# STM_Basic_Extender.net
KiCad netlist of a schematic drawn in EasyEDA Pro
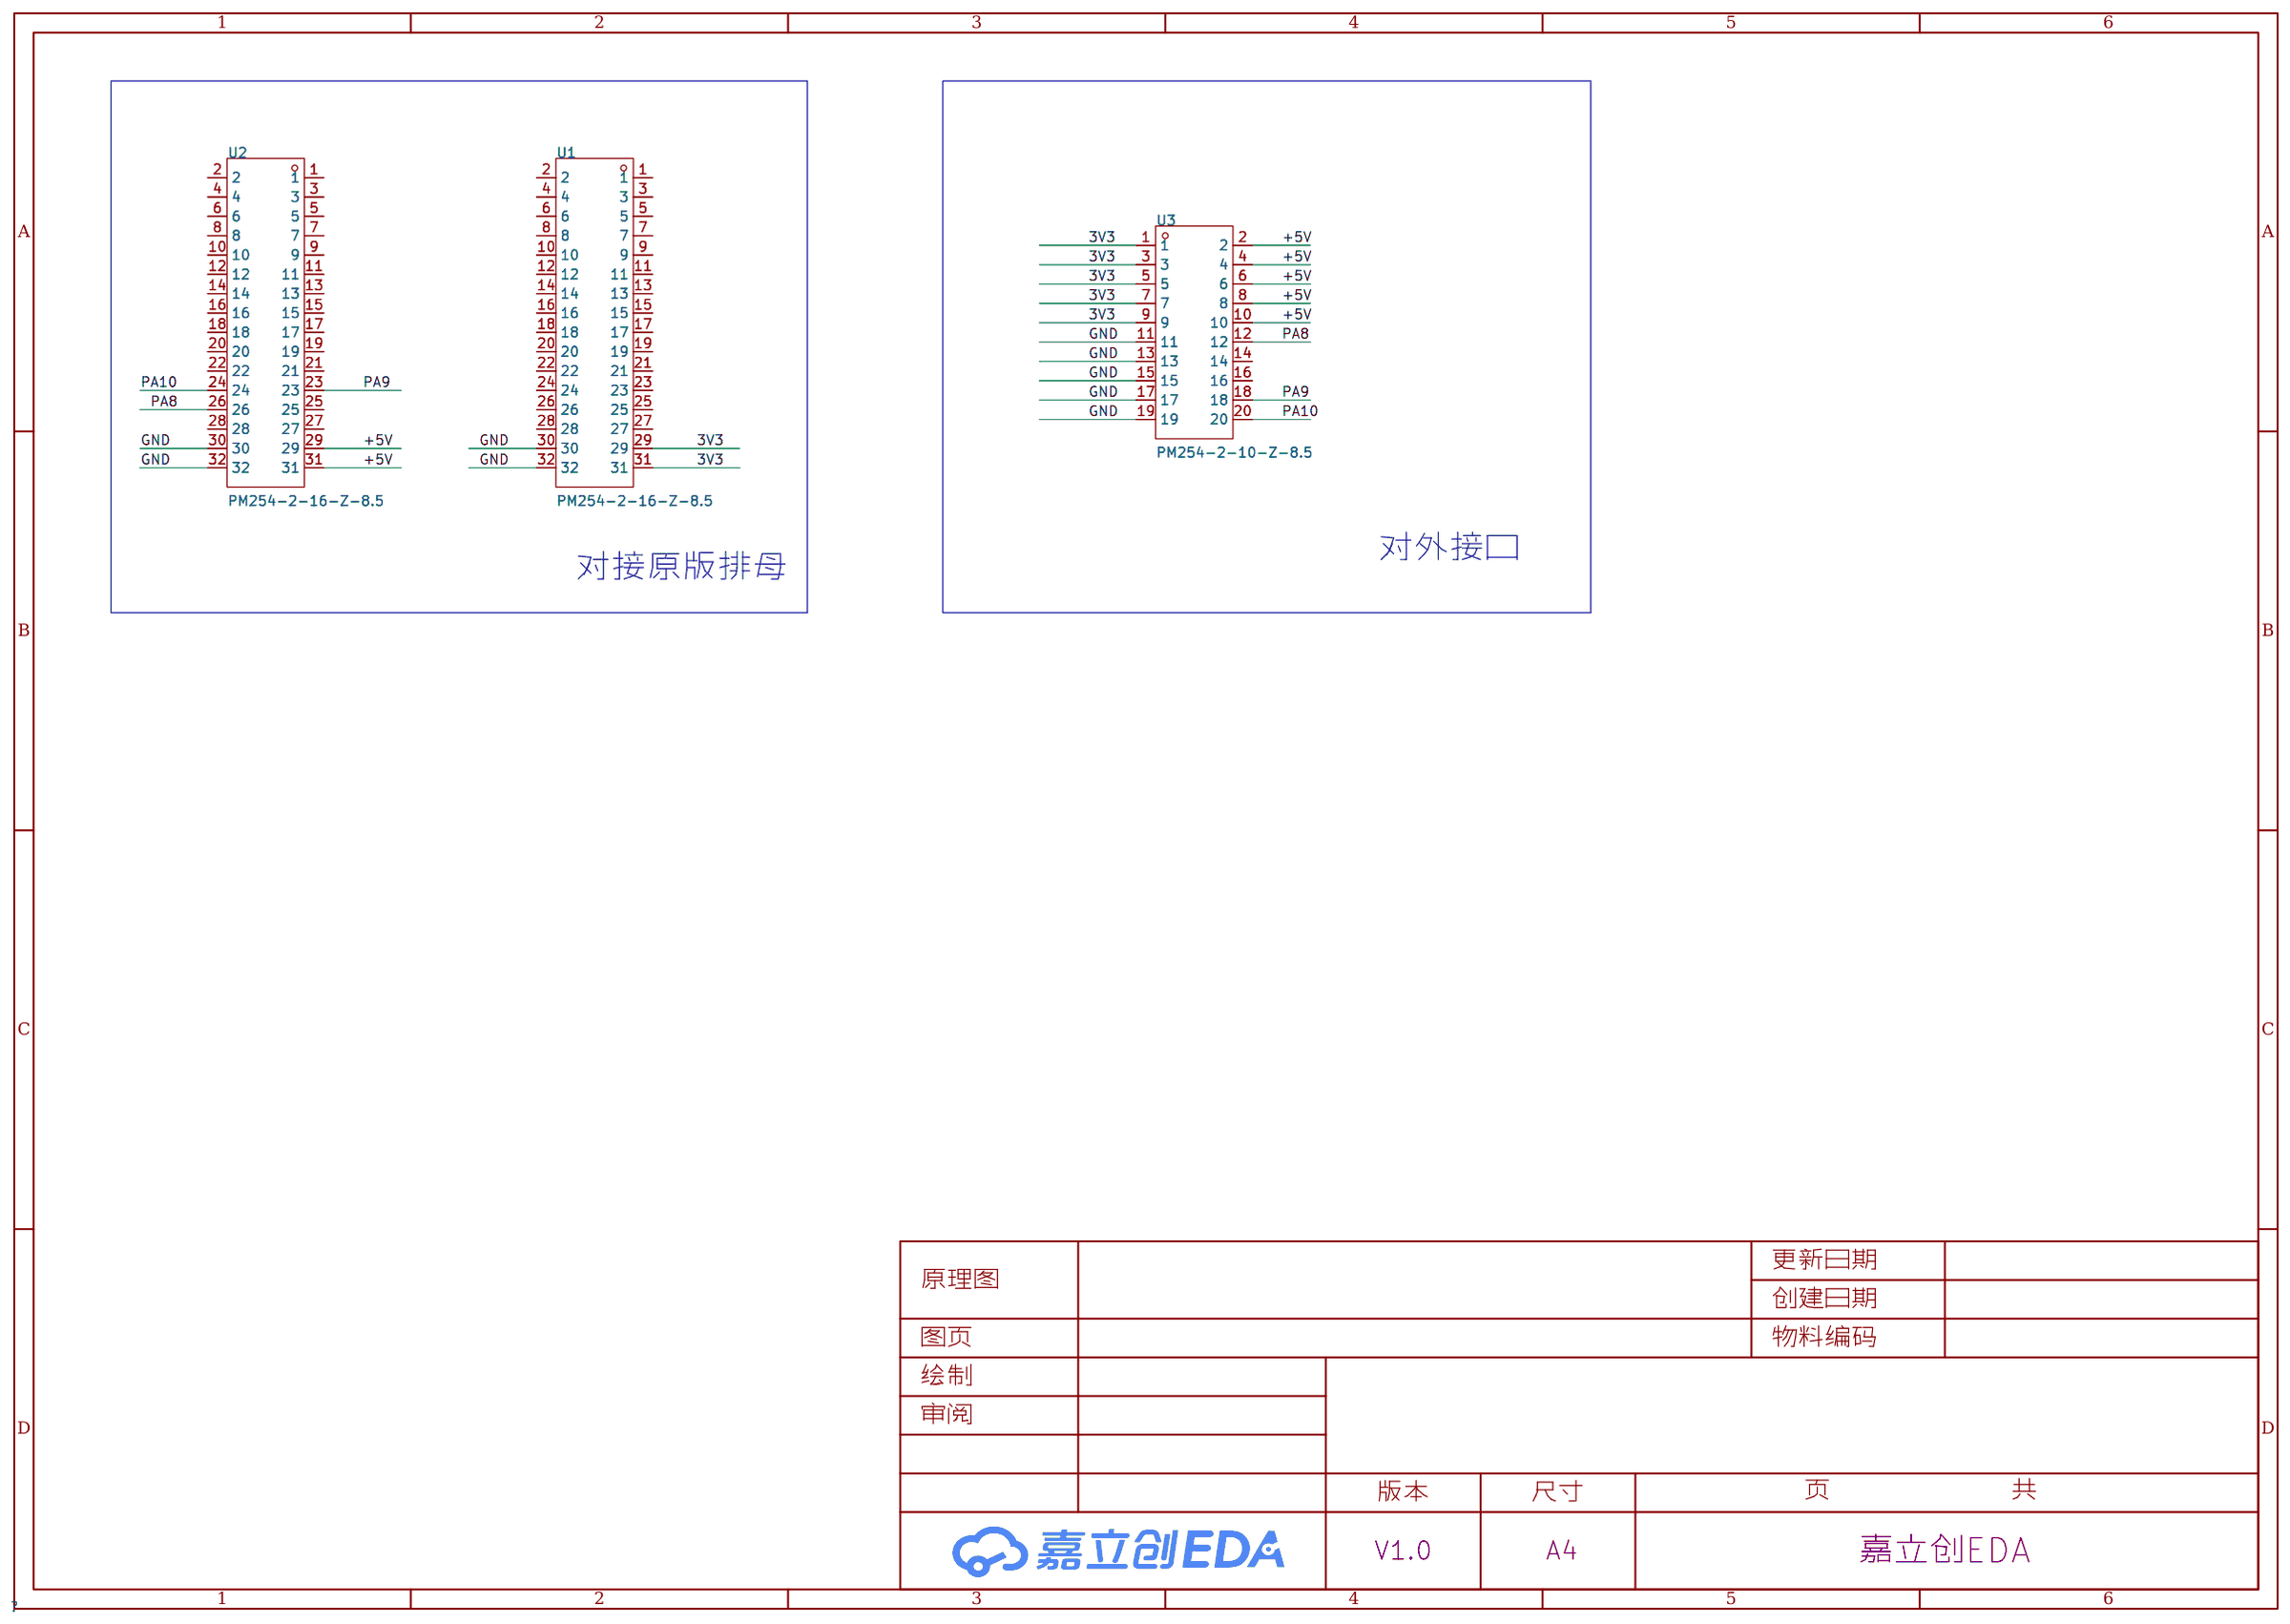
[diagram p0: schematic sheet]

(export (version "E")
  (design (tool "Eeschema 10.0.6"))
  (components
    (comp (ref "U1")
      (value "PM254-2-16-Z-8.5")
      (footprint "easyedapro:HDR-TH_32P-P2.54-V-F-R2-C16-S2.54")
      (fields (field (name "Manufacturer") "HCTL(华灿天禄)"))
      (libsource (lib "easyedapro") (part "PM254-2-16-Z-8.5"))
    )
    (comp (ref "U2")
      (value "PM254-2-16-Z-8.5")
      (footprint "easyedapro:HDR-TH_32P-P2.54-V-F-R2-C16-S2.54")
      (fields (field (name "Manufacturer") "HCTL(华灿天禄)"))
      (libsource (lib "easyedapro") (part "PM254-2-16-Z-8.5"))
    )
    (comp (ref "U3")
      (value "PM254-2-10-Z-8.5")
      (footprint "easyedapro:HDR-TH_20P-P2.54-V-F-R2-C10-S2.54")
      (fields (field (name "Manufacturer") "HCTL(华灿天禄)"))
      (libsource (lib "easyedapro") (part "PM254-2-10-Z-8.5"))
    )
  )
  (nets
    (net (code "1") (name "/+5V") (class "Default")
      (node (ref "U2") (pin "29") (pinfunction "29_29") (pintype "unspecified"))
      (node (ref "U2") (pin "31") (pinfunction "31_31") (pintype "unspecified"))
      (node (ref "U3") (pin "10") (pinfunction "10_10") (pintype "unspecified"))
      (node (ref "U3") (pin "2") (pinfunction "2_2") (pintype "unspecified"))
      (node (ref "U3") (pin "4") (pinfunction "4_4") (pintype "unspecified"))
      (node (ref "U3") (pin "6") (pinfunction "6_6") (pintype "unspecified"))
      (node (ref "U3") (pin "8") (pinfunction "8_8") (pintype "unspecified"))
    )
    (net (code "2") (name "/3V3") (class "Default")
      (node (ref "U1") (pin "29") (pinfunction "29_29") (pintype "unspecified"))
      (node (ref "U1") (pin "31") (pinfunction "31_31") (pintype "unspecified"))
      (node (ref "U3") (pin "1") (pinfunction "1_1") (pintype "unspecified"))
      (node (ref "U3") (pin "3") (pinfunction "3_3") (pintype "unspecified"))
      (node (ref "U3") (pin "5") (pinfunction "5_5") (pintype "unspecified"))
      (node (ref "U3") (pin "7") (pinfunction "7_7") (pintype "unspecified"))
      (node (ref "U3") (pin "9") (pinfunction "9_9") (pintype "unspecified"))
    )
    (net (code "3") (name "/GND") (class "Default")
      (node (ref "U1") (pin "30") (pinfunction "30_30") (pintype "unspecified"))
      (node (ref "U1") (pin "32") (pinfunction "32_32") (pintype "unspecified"))
      (node (ref "U2") (pin "30") (pinfunction "30_30") (pintype "unspecified"))
      (node (ref "U2") (pin "32") (pinfunction "32_32") (pintype "unspecified"))
      (node (ref "U3") (pin "11") (pinfunction "11_11") (pintype "unspecified"))
      (node (ref "U3") (pin "13") (pinfunction "13_13") (pintype "unspecified"))
      (node (ref "U3") (pin "15") (pinfunction "15_15") (pintype "unspecified"))
      (node (ref "U3") (pin "17") (pinfunction "17_17") (pintype "unspecified"))
      (node (ref "U3") (pin "19") (pinfunction "19_19") (pintype "unspecified"))
    )
    (net (code "4") (name "/PA8") (class "Default")
      (node (ref "U2") (pin "26") (pinfunction "26_26") (pintype "unspecified"))
      (node (ref "U3") (pin "12") (pinfunction "12_12") (pintype "unspecified"))
    )
    (net (code "5") (name "/PA9") (class "Default")
      (node (ref "U2") (pin "23") (pinfunction "23_23") (pintype "unspecified"))
      (node (ref "U3") (pin "18") (pinfunction "18_18") (pintype "unspecified"))
    )
    (net (code "6") (name "/PA10") (class "Default")
      (node (ref "U2") (pin "24") (pinfunction "24_24") (pintype "unspecified"))
      (node (ref "U3") (pin "20") (pinfunction "20_20") (pintype "unspecified"))
    )
    (net (code "7") (name "unconnected-(U1-Pad1)") (class "Default")
      (node (ref "U1") (pin "1") (pinfunction "1_1") (pintype "unspecified"))
    )
    (net (code "8") (name "unconnected-(U1-Pad2)") (class "Default")
      (node (ref "U1") (pin "2") (pinfunction "2_2") (pintype "unspecified"))
    )
    (net (code "9") (name "unconnected-(U1-Pad3)") (class "Default")
      (node (ref "U1") (pin "3") (pinfunction "3_3") (pintype "unspecified"))
    )
    (net (code "10") (name "unconnected-(U1-Pad4)") (class "Default")
      (node (ref "U1") (pin "4") (pinfunction "4_4") (pintype "unspecified"))
    )
    (net (code "11") (name "unconnected-(U1-Pad5)") (class "Default")
      (node (ref "U1") (pin "5") (pinfunction "5_5") (pintype "unspecified"))
    )
    (net (code "12") (name "unconnected-(U1-Pad6)") (class "Default")
      (node (ref "U1") (pin "6") (pinfunction "6_6") (pintype "unspecified"))
    )
    (net (code "13") (name "unconnected-(U1-Pad7)") (class "Default")
      (node (ref "U1") (pin "7") (pinfunction "7_7") (pintype "unspecified"))
    )
    (net (code "14") (name "unconnected-(U1-Pad8)") (class "Default")
      (node (ref "U1") (pin "8") (pinfunction "8_8") (pintype "unspecified"))
    )
    (net (code "15") (name "unconnected-(U1-Pad9)") (class "Default")
      (node (ref "U1") (pin "9") (pinfunction "9_9") (pintype "unspecified"))
    )
    (net (code "16") (name "unconnected-(U1-Pad10)") (class "Default")
      (node (ref "U1") (pin "10") (pinfunction "10_10") (pintype "unspecified"))
    )
    (net (code "17") (name "unconnected-(U1-Pad11)") (class "Default")
      (node (ref "U1") (pin "11") (pinfunction "11_11") (pintype "unspecified"))
    )
    (net (code "18") (name "unconnected-(U1-Pad12)") (class "Default")
      (node (ref "U1") (pin "12") (pinfunction "12_12") (pintype "unspecified"))
    )
    (net (code "19") (name "unconnected-(U1-Pad13)") (class "Default")
      (node (ref "U1") (pin "13") (pinfunction "13_13") (pintype "unspecified"))
    )
    (net (code "20") (name "unconnected-(U1-Pad14)") (class "Default")
      (node (ref "U1") (pin "14") (pinfunction "14_14") (pintype "unspecified"))
    )
    (net (code "21") (name "unconnected-(U1-Pad15)") (class "Default")
      (node (ref "U1") (pin "15") (pinfunction "15_15") (pintype "unspecified"))
    )
    (net (code "22") (name "unconnected-(U1-Pad16)") (class "Default")
      (node (ref "U1") (pin "16") (pinfunction "16_16") (pintype "unspecified"))
    )
    (net (code "23") (name "unconnected-(U1-Pad17)") (class "Default")
      (node (ref "U1") (pin "17") (pinfunction "17_17") (pintype "unspecified"))
    )
    (net (code "24") (name "unconnected-(U1-Pad18)") (class "Default")
      (node (ref "U1") (pin "18") (pinfunction "18_18") (pintype "unspecified"))
    )
    (net (code "25") (name "unconnected-(U1-Pad19)") (class "Default")
      (node (ref "U1") (pin "19") (pinfunction "19_19") (pintype "unspecified"))
    )
    (net (code "26") (name "unconnected-(U1-Pad20)") (class "Default")
      (node (ref "U1") (pin "20") (pinfunction "20_20") (pintype "unspecified"))
    )
    (net (code "27") (name "unconnected-(U1-Pad21)") (class "Default")
      (node (ref "U1") (pin "21") (pinfunction "21_21") (pintype "unspecified"))
    )
    (net (code "28") (name "unconnected-(U1-Pad22)") (class "Default")
      (node (ref "U1") (pin "22") (pinfunction "22_22") (pintype "unspecified"))
    )
    (net (code "29") (name "unconnected-(U1-Pad23)") (class "Default")
      (node (ref "U1") (pin "23") (pinfunction "23_23") (pintype "unspecified"))
    )
    (net (code "30") (name "unconnected-(U1-Pad24)") (class "Default")
      (node (ref "U1") (pin "24") (pinfunction "24_24") (pintype "unspecified"))
    )
    (net (code "31") (name "unconnected-(U1-Pad25)") (class "Default")
      (node (ref "U1") (pin "25") (pinfunction "25_25") (pintype "unspecified"))
    )
    (net (code "32") (name "unconnected-(U1-Pad26)") (class "Default")
      (node (ref "U1") (pin "26") (pinfunction "26_26") (pintype "unspecified"))
    )
    (net (code "33") (name "unconnected-(U1-Pad27)") (class "Default")
      (node (ref "U1") (pin "27") (pinfunction "27_27") (pintype "unspecified"))
    )
    (net (code "34") (name "unconnected-(U1-Pad28)") (class "Default")
      (node (ref "U1") (pin "28") (pinfunction "28_28") (pintype "unspecified"))
    )
    (net (code "35") (name "unconnected-(U2-Pad1)") (class "Default")
      (node (ref "U2") (pin "1") (pinfunction "1_1") (pintype "unspecified"))
    )
    (net (code "36") (name "unconnected-(U2-Pad2)") (class "Default")
      (node (ref "U2") (pin "2") (pinfunction "2_2") (pintype "unspecified"))
    )
    (net (code "37") (name "unconnected-(U2-Pad3)") (class "Default")
      (node (ref "U2") (pin "3") (pinfunction "3_3") (pintype "unspecified"))
    )
    (net (code "38") (name "unconnected-(U2-Pad4)") (class "Default")
      (node (ref "U2") (pin "4") (pinfunction "4_4") (pintype "unspecified"))
    )
    (net (code "39") (name "unconnected-(U2-Pad5)") (class "Default")
      (node (ref "U2") (pin "5") (pinfunction "5_5") (pintype "unspecified"))
    )
    (net (code "40") (name "unconnected-(U2-Pad6)") (class "Default")
      (node (ref "U2") (pin "6") (pinfunction "6_6") (pintype "unspecified"))
    )
    (net (code "41") (name "unconnected-(U2-Pad7)") (class "Default")
      (node (ref "U2") (pin "7") (pinfunction "7_7") (pintype "unspecified"))
    )
    (net (code "42") (name "unconnected-(U2-Pad8)") (class "Default")
      (node (ref "U2") (pin "8") (pinfunction "8_8") (pintype "unspecified"))
    )
    (net (code "43") (name "unconnected-(U2-Pad9)") (class "Default")
      (node (ref "U2") (pin "9") (pinfunction "9_9") (pintype "unspecified"))
    )
    (net (code "44") (name "unconnected-(U2-Pad10)") (class "Default")
      (node (ref "U2") (pin "10") (pinfunction "10_10") (pintype "unspecified"))
    )
    (net (code "45") (name "unconnected-(U2-Pad11)") (class "Default")
      (node (ref "U2") (pin "11") (pinfunction "11_11") (pintype "unspecified"))
    )
    (net (code "46") (name "unconnected-(U2-Pad12)") (class "Default")
      (node (ref "U2") (pin "12") (pinfunction "12_12") (pintype "unspecified"))
    )
    (net (code "47") (name "unconnected-(U2-Pad13)") (class "Default")
      (node (ref "U2") (pin "13") (pinfunction "13_13") (pintype "unspecified"))
    )
    (net (code "48") (name "unconnected-(U2-Pad14)") (class "Default")
      (node (ref "U2") (pin "14") (pinfunction "14_14") (pintype "unspecified"))
    )
    (net (code "49") (name "unconnected-(U2-Pad15)") (class "Default")
      (node (ref "U2") (pin "15") (pinfunction "15_15") (pintype "unspecified"))
    )
    (net (code "50") (name "unconnected-(U2-Pad16)") (class "Default")
      (node (ref "U2") (pin "16") (pinfunction "16_16") (pintype "unspecified"))
    )
    (net (code "51") (name "unconnected-(U2-Pad17)") (class "Default")
      (node (ref "U2") (pin "17") (pinfunction "17_17") (pintype "unspecified"))
    )
    (net (code "52") (name "unconnected-(U2-Pad18)") (class "Default")
      (node (ref "U2") (pin "18") (pinfunction "18_18") (pintype "unspecified"))
    )
    (net (code "53") (name "unconnected-(U2-Pad19)") (class "Default")
      (node (ref "U2") (pin "19") (pinfunction "19_19") (pintype "unspecified"))
    )
    (net (code "54") (name "unconnected-(U2-Pad20)") (class "Default")
      (node (ref "U2") (pin "20") (pinfunction "20_20") (pintype "unspecified"))
    )
    (net (code "55") (name "unconnected-(U2-Pad21)") (class "Default")
      (node (ref "U2") (pin "21") (pinfunction "21_21") (pintype "unspecified"))
    )
    (net (code "56") (name "unconnected-(U2-Pad22)") (class "Default")
      (node (ref "U2") (pin "22") (pinfunction "22_22") (pintype "unspecified"))
    )
    (net (code "57") (name "unconnected-(U2-Pad25)") (class "Default")
      (node (ref "U2") (pin "25") (pinfunction "25_25") (pintype "unspecified"))
    )
    (net (code "58") (name "unconnected-(U2-Pad27)") (class "Default")
      (node (ref "U2") (pin "27") (pinfunction "27_27") (pintype "unspecified"))
    )
    (net (code "59") (name "unconnected-(U2-Pad28)") (class "Default")
      (node (ref "U2") (pin "28") (pinfunction "28_28") (pintype "unspecified"))
    )
    (net (code "60") (name "unconnected-(U3-Pad14)") (class "Default")
      (node (ref "U3") (pin "14") (pinfunction "14_14") (pintype "unspecified"))
    )
    (net (code "61") (name "unconnected-(U3-Pad16)") (class "Default")
      (node (ref "U3") (pin "16") (pinfunction "16_16") (pintype "unspecified"))
    )
  )
)
